# main_pinout.net
KiCad netlist of a schematic drawn in Altium Designer
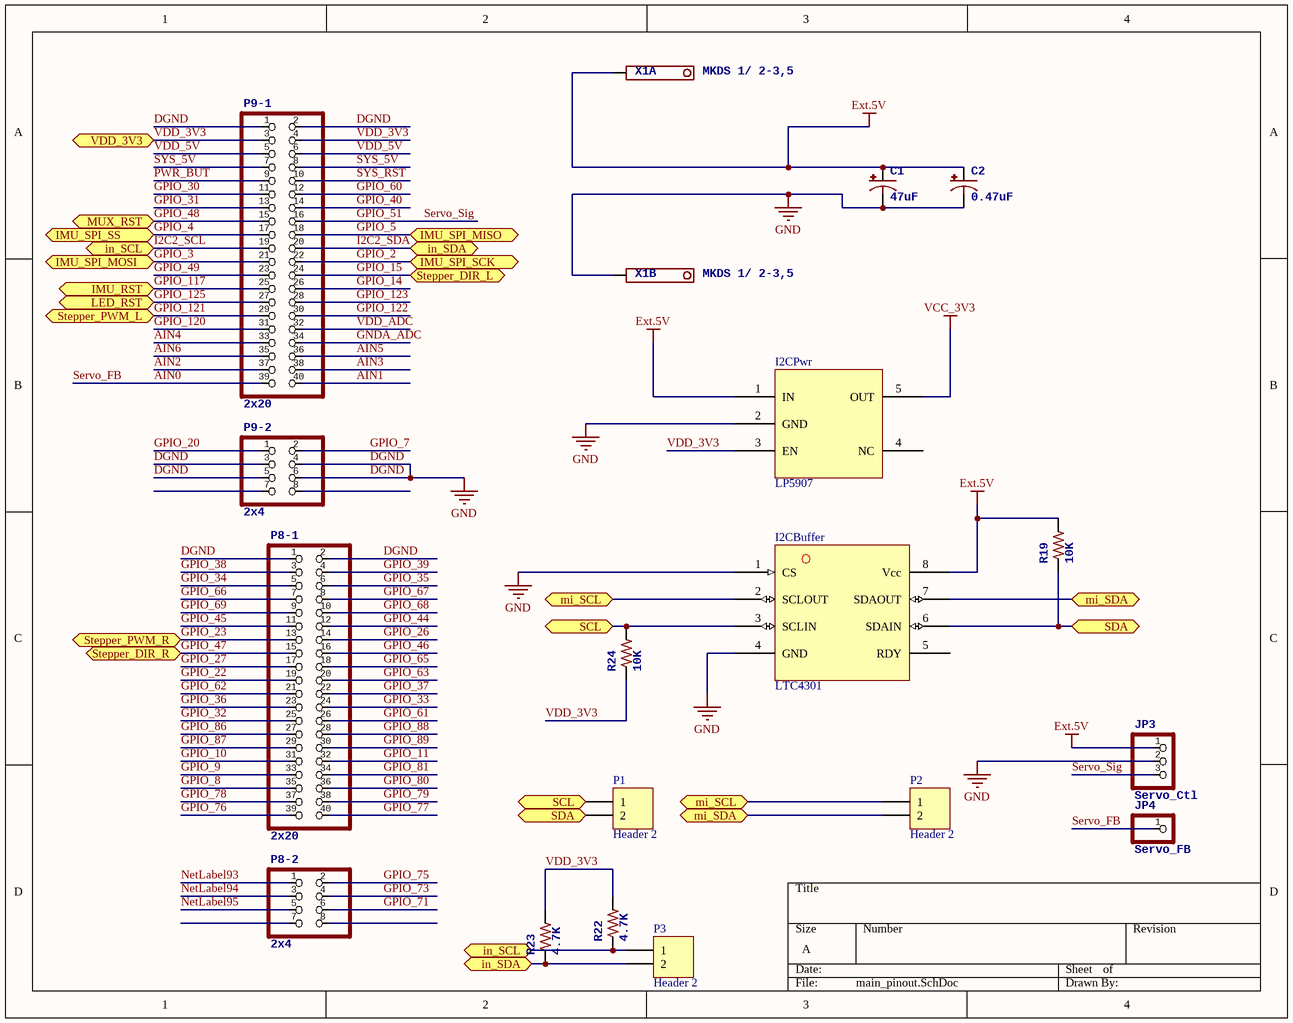
[diagram p0: main_pinout.SchDoc]

(export (version "E")
  (design (tool "Eeschema 10.0.6"))
  (components
    (comp (ref "C1") (value "47uF") (footprint "E2,5-7") (libsource (lib "adafruit") (part "CPOL-USE2.5-7")))
    (comp (ref "C2") (value "0.47uF") (footprint "E5-6") (libsource (lib "adafruit") (part "CPOL-USE5-6")))
    (comp (ref "I2CBuffer")
      (value "LTC4301")
      (footprint "TSSOP-8")
      (libsource (lib "KLibrary") (part "LTC4301"))
    )
    (comp (ref "I2CPwr") (value "LP5907") (footprint "SOT23-5L") (libsource (lib "KLibrary") (part "LP5907")))
    (comp (ref "JP3") (value "Servo_Ctl") (footprint "1X03") (libsource (lib "adafruit") (part "PINHD-1X3")))
    (comp (ref "JP4") (value "Servo_FB") (footprint "1X01") (libsource (lib "adafruit") (part "PINHD-1X1")))
    (comp (ref "P1")
      (value "Header 2")
      (footprint "HDR1X2")
      (description "Header, 2-Pin")
      (fields (field (name "PUBLISHER") "Altium Limited"))
      (libsource (lib "Miscellaneous Connectors") (part "Header 2"))
    )
    (comp (ref "P2")
      (value "Header 2")
      (footprint "HDR1X2")
      (description "Header, 2-Pin")
      (fields (field (name "PUBLISHER") "Altium Limited"))
      (libsource (lib "Miscellaneous Connectors") (part "Header 2"))
    )
    (comp (ref "P3")
      (value "Header 2")
      (footprint "HDR1X2")
      (description "Header, 2-Pin")
      (fields (field (name "PUBLISHER") "Altium Limited"))
      (libsource (lib "Miscellaneous Connectors") (part "Header 2"))
    )
    (comp (ref "P8-1") (value "2x20") (footprint "2X20") (libsource (lib "adafruit") (part "PINHD-2X20")))
    (comp (ref "P8-2") (value "2x4") (footprint "2X04") (libsource (lib "adafruit") (part "PINHD-2X4")))
    (comp (ref "P9-1") (value "2x20") (footprint "2X20") (libsource (lib "adafruit") (part "PINHD-2X20")))
    (comp (ref "P9-2") (value "2x4") (footprint "2X04") (libsource (lib "adafruit") (part "PINHD-2X4")))
    (comp (ref "R19") (value "10K") (footprint "R0805") (libsource (lib "adafruit") (part "R-US_R0805")))
    (comp (ref "R22") (value "4.7K") (footprint "R0805") (libsource (lib "adafruit") (part "R-US_R0805")))
    (comp (ref "R23") (value "4.7K") (footprint "R0805") (libsource (lib "adafruit") (part "R-US_R0805")))
    (comp (ref "R24") (value "10K") (footprint "R0805") (libsource (lib "adafruit") (part "R-US_R0805")))
    (comp (ref "X1")
      (value "MKDS 1/ 2-3,5")
      (footprint "1751248")
      (libsource (lib "con-phoenix-350") (part "1751248"))
    )
  )
  (nets
    (net (code "1") (name "/AIN0") (class "Default")
      (node (ref "JP4") (pin "1") (pinfunction "1_1") (pintype "passive"))
      (node (ref "P9-1") (pin "39") (pinfunction "39_39") (pintype "passive"))
    )
    (net (code "2") (name "/AIN1") (class "Default")
      (node (ref "P9-1") (pin "40") (pinfunction "40_40") (pintype "passive"))
    )
    (net (code "3") (name "/AIN2") (class "Default")
      (node (ref "P9-1") (pin "37") (pinfunction "37_37") (pintype "passive"))
    )
    (net (code "4") (name "/AIN3") (class "Default")
      (node (ref "P9-1") (pin "38") (pinfunction "38_38") (pintype "passive"))
    )
    (net (code "5") (name "/AIN4") (class "Default")
      (node (ref "P9-1") (pin "33") (pinfunction "33_33") (pintype "passive"))
    )
    (net (code "6") (name "/AIN5") (class "Default")
      (node (ref "P9-1") (pin "36") (pinfunction "36_36") (pintype "passive"))
    )
    (net (code "7") (name "/AIN6") (class "Default")
      (node (ref "P9-1") (pin "35") (pinfunction "35_35") (pintype "passive"))
    )
    (net (code "8") (name "/GNDA_ADC") (class "Default")
      (node (ref "P9-1") (pin "34") (pinfunction "34_34") (pintype "passive"))
    )
    (net (code "9") (name "/GPIO_2") (class "Default")
      (node (ref "P9-1") (pin "22") (pinfunction "22_22") (pintype "passive"))
    )
    (net (code "10") (name "/GPIO_3") (class "Default")
      (node (ref "P9-1") (pin "21") (pinfunction "21_21") (pintype "passive"))
    )
    (net (code "11") (name "/GPIO_4") (class "Default")
      (node (ref "P9-1") (pin "17") (pinfunction "17_17") (pintype "passive"))
    )
    (net (code "12") (name "/GPIO_5") (class "Default")
      (node (ref "P9-1") (pin "18") (pinfunction "18_18") (pintype "passive"))
    )
    (net (code "13") (name "/GPIO_7") (class "Default")
      (node (ref "P9-2") (pin "2") (pinfunction "2_2") (pintype "passive"))
    )
    (net (code "14") (name "/GPIO_8") (class "Default")
      (node (ref "P8-1") (pin "35") (pinfunction "35_35") (pintype "passive"))
    )
    (net (code "15") (name "/GPIO_9") (class "Default")
      (node (ref "P8-1") (pin "33") (pinfunction "33_33") (pintype "passive"))
    )
    (net (code "16") (name "/GPIO_10") (class "Default")
      (node (ref "P8-1") (pin "31") (pinfunction "31_31") (pintype "passive"))
    )
    (net (code "17") (name "/GPIO_11") (class "Default")
      (node (ref "P8-1") (pin "32") (pinfunction "32_32") (pintype "passive"))
    )
    (net (code "18") (name "/GPIO_14") (class "Default")
      (node (ref "P9-1") (pin "26") (pinfunction "26_26") (pintype "passive"))
    )
    (net (code "19") (name "/GPIO_15") (class "Default")
      (node (ref "P9-1") (pin "24") (pinfunction "24_24") (pintype "passive"))
    )
    (net (code "20") (name "/GPIO_20") (class "Default")
      (node (ref "P9-2") (pin "1") (pinfunction "1_1") (pintype "passive"))
    )
    (net (code "21") (name "/GPIO_22") (class "Default")
      (node (ref "P8-1") (pin "19") (pinfunction "19_19") (pintype "passive"))
    )
    (net (code "22") (name "/GPIO_23") (class "Default")
      (node (ref "P8-1") (pin "13") (pinfunction "13_13") (pintype "passive"))
    )
    (net (code "23") (name "/GPIO_26") (class "Default")
      (node (ref "P8-1") (pin "14") (pinfunction "14_14") (pintype "passive"))
    )
    (net (code "24") (name "/GPIO_27") (class "Default")
      (node (ref "P8-1") (pin "17") (pinfunction "17_17") (pintype "passive"))
    )
    (net (code "25") (name "/GPIO_30") (class "Default")
      (node (ref "P9-1") (pin "11") (pinfunction "11_11") (pintype "passive"))
    )
    (net (code "26") (name "/GPIO_31") (class "Default")
      (node (ref "P9-1") (pin "13") (pinfunction "13_13") (pintype "passive"))
    )
    (net (code "27") (name "/GPIO_32") (class "Default")
      (node (ref "P8-1") (pin "25") (pinfunction "25_25") (pintype "passive"))
    )
    (net (code "28") (name "/GPIO_33") (class "Default")
      (node (ref "P8-1") (pin "24") (pinfunction "24_24") (pintype "passive"))
    )
    (net (code "29") (name "/GPIO_34") (class "Default")
      (node (ref "P8-1") (pin "5") (pinfunction "5_5") (pintype "passive"))
    )
    (net (code "30") (name "/GPIO_35") (class "Default")
      (node (ref "P8-1") (pin "6") (pinfunction "6_6") (pintype "passive"))
    )
    (net (code "31") (name "/GPIO_36") (class "Default")
      (node (ref "P8-1") (pin "23") (pinfunction "23_23") (pintype "passive"))
    )
    (net (code "32") (name "/GPIO_37") (class "Default")
      (node (ref "P8-1") (pin "22") (pinfunction "22_22") (pintype "passive"))
    )
    (net (code "33") (name "/GPIO_38") (class "Default")
      (node (ref "P8-1") (pin "3") (pinfunction "3_3") (pintype "passive"))
    )
    (net (code "34") (name "/GPIO_39") (class "Default")
      (node (ref "P8-1") (pin "4") (pinfunction "4_4") (pintype "passive"))
    )
    (net (code "35") (name "/GPIO_40") (class "Default")
      (node (ref "P9-1") (pin "14") (pinfunction "14_14") (pintype "passive"))
    )
    (net (code "36") (name "/GPIO_44") (class "Default")
      (node (ref "P8-1") (pin "12") (pinfunction "12_12") (pintype "passive"))
    )
    (net (code "37") (name "/GPIO_45") (class "Default")
      (node (ref "P8-1") (pin "11") (pinfunction "11_11") (pintype "passive"))
    )
    (net (code "38") (name "/GPIO_46") (class "Default")
      (node (ref "P8-1") (pin "16") (pinfunction "16_16") (pintype "passive"))
    )
    (net (code "39") (name "/GPIO_47") (class "Default")
      (node (ref "P8-1") (pin "15") (pinfunction "15_15") (pintype "passive"))
    )
    (net (code "40") (name "/GPIO_48") (class "Default")
      (node (ref "P9-1") (pin "15") (pinfunction "15_15") (pintype "passive"))
    )
    (net (code "41") (name "/GPIO_49") (class "Default")
      (node (ref "P9-1") (pin "23") (pinfunction "23_23") (pintype "passive"))
    )
    (net (code "42") (name "/GPIO_51") (class "Default")
      (node (ref "JP3") (pin "3") (pinfunction "3_3") (pintype "passive"))
      (node (ref "P9-1") (pin "16") (pinfunction "16_16") (pintype "passive"))
    )
    (net (code "43") (name "/GPIO_60") (class "Default")
      (node (ref "P9-1") (pin "12") (pinfunction "12_12") (pintype "passive"))
    )
    (net (code "44") (name "/GPIO_61") (class "Default")
      (node (ref "P8-1") (pin "26") (pinfunction "26_26") (pintype "passive"))
    )
    (net (code "45") (name "/GPIO_62") (class "Default")
      (node (ref "P8-1") (pin "21") (pinfunction "21_21") (pintype "passive"))
    )
    (net (code "46") (name "/GPIO_63") (class "Default")
      (node (ref "P8-1") (pin "20") (pinfunction "20_20") (pintype "passive"))
    )
    (net (code "47") (name "/GPIO_65") (class "Default")
      (node (ref "P8-1") (pin "18") (pinfunction "18_18") (pintype "passive"))
    )
    (net (code "48") (name "/GPIO_66") (class "Default")
      (node (ref "P8-1") (pin "7") (pinfunction "7_7") (pintype "passive"))
    )
    (net (code "49") (name "/GPIO_67") (class "Default")
      (node (ref "P8-1") (pin "8") (pinfunction "8_8") (pintype "passive"))
    )
    (net (code "50") (name "/GPIO_68") (class "Default")
      (node (ref "P8-1") (pin "10") (pinfunction "10_10") (pintype "passive"))
    )
    (net (code "51") (name "/GPIO_69") (class "Default")
      (node (ref "P8-1") (pin "9") (pinfunction "9_9") (pintype "passive"))
    )
    (net (code "52") (name "/GPIO_71") (class "Default")
      (node (ref "P8-2") (pin "6") (pinfunction "6_6") (pintype "passive"))
    )
    (net (code "53") (name "/GPIO_73") (class "Default")
      (node (ref "P8-2") (pin "4") (pinfunction "4_4") (pintype "passive"))
    )
    (net (code "54") (name "/GPIO_75") (class "Default")
      (node (ref "P8-2") (pin "2") (pinfunction "2_2") (pintype "passive"))
    )
    (net (code "55") (name "/GPIO_76") (class "Default")
      (node (ref "P8-1") (pin "39") (pinfunction "39_39") (pintype "passive"))
    )
    (net (code "56") (name "/GPIO_77") (class "Default")
      (node (ref "P8-1") (pin "40") (pinfunction "40_40") (pintype "passive"))
    )
    (net (code "57") (name "/GPIO_78") (class "Default")
      (node (ref "P8-1") (pin "37") (pinfunction "37_37") (pintype "passive"))
    )
    (net (code "58") (name "/GPIO_79") (class "Default")
      (node (ref "P8-1") (pin "38") (pinfunction "38_38") (pintype "passive"))
    )
    (net (code "59") (name "/GPIO_80") (class "Default")
      (node (ref "P8-1") (pin "36") (pinfunction "36_36") (pintype "passive"))
    )
    (net (code "60") (name "/GPIO_81") (class "Default")
      (node (ref "P8-1") (pin "34") (pinfunction "34_34") (pintype "passive"))
    )
    (net (code "61") (name "/GPIO_86") (class "Default")
      (node (ref "P8-1") (pin "27") (pinfunction "27_27") (pintype "passive"))
    )
    (net (code "62") (name "/GPIO_87") (class "Default")
      (node (ref "P8-1") (pin "29") (pinfunction "29_29") (pintype "passive"))
    )
    (net (code "63") (name "/GPIO_88") (class "Default")
      (node (ref "P8-1") (pin "28") (pinfunction "28_28") (pintype "passive"))
    )
    (net (code "64") (name "/GPIO_89") (class "Default")
      (node (ref "P8-1") (pin "30") (pinfunction "30_30") (pintype "passive"))
    )
    (net (code "65") (name "/GPIO_117") (class "Default")
      (node (ref "P9-1") (pin "25") (pinfunction "25_25") (pintype "passive"))
    )
    (net (code "66") (name "/GPIO_120") (class "Default")
      (node (ref "P9-1") (pin "31") (pinfunction "31_31") (pintype "passive"))
    )
    (net (code "67") (name "/GPIO_121") (class "Default")
      (node (ref "P9-1") (pin "29") (pinfunction "29_29") (pintype "passive"))
    )
    (net (code "68") (name "/GPIO_122") (class "Default")
      (node (ref "P9-1") (pin "30") (pinfunction "30_30") (pintype "passive"))
    )
    (net (code "69") (name "/GPIO_123") (class "Default")
      (node (ref "P9-1") (pin "28") (pinfunction "28_28") (pintype "passive"))
    )
    (net (code "70") (name "/GPIO_125") (class "Default")
      (node (ref "P9-1") (pin "27") (pinfunction "27_27") (pintype "passive"))
    )
    (net (code "71") (name "/I2C2_SCL") (class "Default")
      (node (ref "P3") (pin "1") (pinfunction "1_1") (pintype "passive"))
      (node (ref "P9-1") (pin "19") (pinfunction "19_19") (pintype "passive"))
      (node (ref "R22") (pin "1") (pinfunction "1_1") (pintype "passive"))
    )
    (net (code "72") (name "/I2C2_SDA") (class "Default")
      (node (ref "P3") (pin "2") (pinfunction "2_2") (pintype "passive"))
      (node (ref "P9-1") (pin "20") (pinfunction "20_20") (pintype "passive"))
      (node (ref "R23") (pin "1") (pinfunction "1_1") (pintype "passive"))
    )
    (net (code "73") (name "/NetLabel93") (class "Default")
      (node (ref "P8-2") (pin "1") (pinfunction "1_1") (pintype "passive"))
    )
    (net (code "74") (name "/NetLabel94") (class "Default")
      (node (ref "P8-2") (pin "3") (pinfunction "3_3") (pintype "passive"))
    )
    (net (code "75") (name "/NetLabel95") (class "Default")
      (node (ref "P8-2") (pin "5") (pinfunction "5_5") (pintype "passive"))
    )
    (net (code "76") (name "/PWR_BUT") (class "Default")
      (node (ref "P9-1") (pin "9") (pinfunction "9_9") (pintype "passive"))
    )
    (net (code "77") (name "/SCL") (class "Default")
      (node (ref "I2CBuffer") (pin "3") (pinfunction "SCLIN_3") (pintype "bidirectional"))
      (node (ref "P1") (pin "1") (pinfunction "1_1") (pintype "passive"))
      (node (ref "R24") (pin "2") (pinfunction "2_2") (pintype "passive"))
    )
    (net (code "78") (name "/SDA") (class "Default")
      (node (ref "I2CBuffer") (pin "6") (pinfunction "SDAIN_6") (pintype "bidirectional"))
      (node (ref "P1") (pin "2") (pinfunction "2_2") (pintype "passive"))
      (node (ref "R19") (pin "1") (pinfunction "1_1") (pintype "passive"))
    )
    (net (code "79") (name "/SYS_5V") (class "Default")
      (node (ref "P9-1") (pin "7") (pinfunction "7_7") (pintype "passive"))
      (node (ref "P9-1") (pin "8") (pinfunction "8_8") (pintype "passive"))
    )
    (net (code "80") (name "/SYS_RST") (class "Default")
      (node (ref "P9-1") (pin "10") (pinfunction "10_10") (pintype "passive"))
    )
    (net (code "81") (name "/VDD_3V3") (class "Default")
      (node (ref "I2CPwr") (pin "3") (pinfunction "EN_3") (pintype "passive"))
      (node (ref "P9-1") (pin "3") (pinfunction "3_3") (pintype "passive"))
      (node (ref "P9-1") (pin "4") (pinfunction "4_4") (pintype "passive"))
      (node (ref "R22") (pin "2") (pinfunction "2_2") (pintype "passive"))
      (node (ref "R23") (pin "2") (pinfunction "2_2") (pintype "passive"))
      (node (ref "R24") (pin "1") (pinfunction "1_1") (pintype "passive"))
    )
    (net (code "82") (name "/VDD_5V") (class "Default")
      (node (ref "P9-1") (pin "5") (pinfunction "5_5") (pintype "passive"))
      (node (ref "P9-1") (pin "6") (pinfunction "6_6") (pintype "passive"))
    )
    (net (code "83") (name "/VDD_ADC") (class "Default")
      (node (ref "P9-1") (pin "32") (pinfunction "32_32") (pintype "passive"))
    )
    (net (code "84") (name "/mi_SCL") (class "Default")
      (node (ref "I2CBuffer") (pin "2") (pinfunction "SCLOUT_2") (pintype "bidirectional"))
      (node (ref "P2") (pin "1") (pinfunction "1_1") (pintype "passive"))
    )
    (net (code "85") (name "/mi_SDA") (class "Default")
      (node (ref "I2CBuffer") (pin "7") (pinfunction "SDAOUT_7") (pintype "bidirectional"))
      (node (ref "P2") (pin "2") (pinfunction "2_2") (pintype "passive"))
    )
    (net (code "86") (name "Ext.5V") (class "Default")
      (node (ref "C1") (pin "+") (pinfunction "+_+") (pintype "passive"))
      (node (ref "C2") (pin "+") (pinfunction "+_+") (pintype "passive"))
      (node (ref "I2CBuffer") (pin "8") (pinfunction "Vcc_8") (pintype "power_in"))
      (node (ref "I2CPwr") (pin "1") (pinfunction "IN_1") (pintype "passive"))
      (node (ref "JP3") (pin "1") (pinfunction "1_1") (pintype "passive"))
      (node (ref "R19") (pin "2") (pinfunction "2_2") (pintype "passive"))
      (node (ref "X1") (pin "1") (pinfunction "K_1") (pintype "passive"))
    )
    (net (code "87") (name "GND") (class "Default")
      (node (ref "C1") (pin "-") (pinfunction "-_-") (pintype "passive"))
      (node (ref "C2") (pin "-") (pinfunction "-_-") (pintype "passive"))
      (node (ref "I2CBuffer") (pin "1") (pinfunction "CS_1") (pintype "input"))
      (node (ref "I2CBuffer") (pin "4") (pinfunction "GND_4") (pintype "power_in"))
      (node (ref "I2CPwr") (pin "2") (pinfunction "GND_2") (pintype "passive"))
      (node (ref "JP3") (pin "2") (pinfunction "2_2") (pintype "passive"))
      (node (ref "P8-1") (pin "1") (pinfunction "1_1") (pintype "passive"))
      (node (ref "P8-1") (pin "2") (pinfunction "2_2") (pintype "passive"))
      (node (ref "P9-1") (pin "1") (pinfunction "1_1") (pintype "passive"))
      (node (ref "P9-1") (pin "2") (pinfunction "2_2") (pintype "passive"))
      (node (ref "P9-2") (pin "3") (pinfunction "3_3") (pintype "passive"))
      (node (ref "P9-2") (pin "4") (pinfunction "4_4") (pintype "passive"))
      (node (ref "P9-2") (pin "5") (pinfunction "5_5") (pintype "passive"))
      (node (ref "P9-2") (pin "6") (pinfunction "6_6") (pintype "passive"))
      (node (ref "X1") (pin "2") (pinfunction "K_2") (pintype "passive"))
    )
    (net (code "88") (name "VCC_3V3") (class "Default")
      (node (ref "I2CPwr") (pin "5") (pinfunction "OUT_5") (pintype "passive"))
    )
    (net (code "89") (name "unconnected-(I2CBuffer-RDY-Pad5)") (class "Default")
      (node (ref "I2CBuffer") (pin "5") (pinfunction "RDY_5") (pintype "passive"))
    )
    (net (code "90") (name "unconnected-(I2CPwr-NC-Pad4)") (class "Default")
      (node (ref "I2CPwr") (pin "4") (pinfunction "NC_4") (pintype "passive"))
    )
    (net (code "91") (name "unconnected-(P8-2-Pad7)") (class "Default")
      (node (ref "P8-2") (pin "7") (pinfunction "7_7") (pintype "passive"))
    )
    (net (code "92") (name "unconnected-(P8-2-Pad8)") (class "Default")
      (node (ref "P8-2") (pin "8") (pinfunction "8_8") (pintype "passive"))
    )
    (net (code "93") (name "unconnected-(P9-2-Pad7)") (class "Default")
      (node (ref "P9-2") (pin "7") (pinfunction "7_7") (pintype "passive"))
    )
    (net (code "94") (name "unconnected-(P9-2-Pad8)") (class "Default")
      (node (ref "P9-2") (pin "8") (pinfunction "8_8") (pintype "passive"))
    )
  )
)
